# 32u4_Xbee_Shield.net
KiCad netlist of a schematic drawn in EAGLE
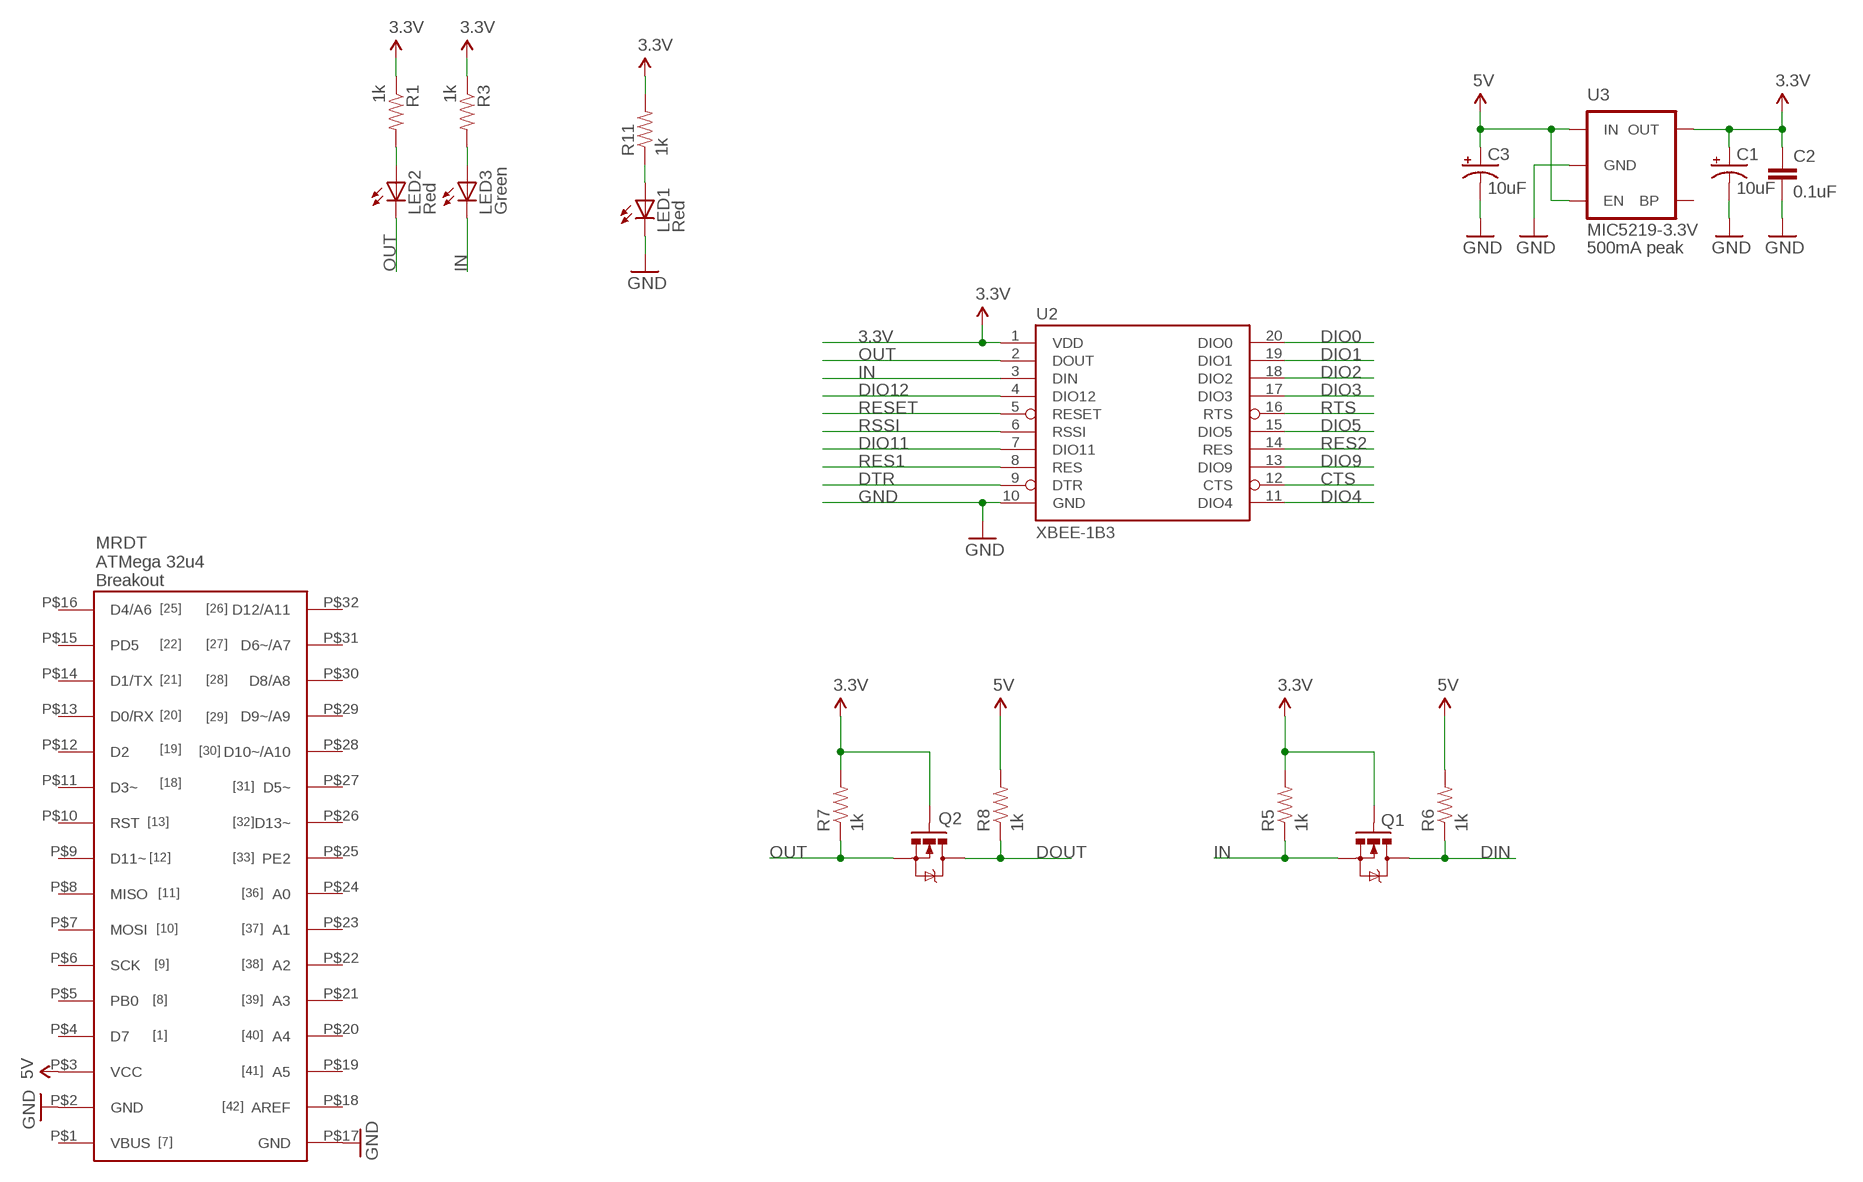
[diagram p0: schematic, sheet 1]

(export (version "E")
  (design (tool "Eeschema 10.0.6"))
  (components
    (comp (ref "C1")
      (value "10uF")
      (footprint "eagle-import:EIA3216")
      (libsource (lib "eagle-import") (part "CAP_POL1206"))
    )
    (comp (ref "C2")
      (value "0.1uF")
      (footprint "eagle-import:1206")
      (libsource (lib "eagle-import") (part "CAP1206"))
    )
    (comp (ref "C3")
      (value "10uF")
      (footprint "eagle-import:EIA3216")
      (libsource (lib "eagle-import") (part "CAP_POL1206"))
    )
    (comp (ref "LED1")
      (value "Red")
      (footprint "eagle-import:LED-0603")
      (libsource (lib "eagle-import") (part "LED0603"))
    )
    (comp (ref "LED2")
      (value "Red")
      (footprint "eagle-import:LED-0603")
      (libsource (lib "eagle-import") (part "LED0603"))
    )
    (comp (ref "LED3")
      (value "Green")
      (footprint "eagle-import:LED-0603")
      (libsource (lib "eagle-import") (part "LED0603"))
    )
    (comp (ref "Q1")
      (value "MOSFET-NCHANNELSMD")
      (footprint "eagle-import:SOT23-3")
      (libsource (lib "eagle-import") (part "MOSFET-NCHANNELSMD"))
    )
    (comp (ref "Q2")
      (value "MOSFET-NCHANNELSMD")
      (footprint "eagle-import:SOT23-3")
      (libsource (lib "eagle-import") (part "MOSFET-NCHANNELSMD"))
    )
    (comp (ref "R1")
      (value "1k")
      (footprint "eagle-import:1206")
      (libsource (lib "eagle-import") (part "RESISTOR1206"))
    )
    (comp (ref "R3")
      (value "1k")
      (footprint "eagle-import:1206")
      (libsource (lib "eagle-import") (part "RESISTOR1206"))
    )
    (comp (ref "R5")
      (value "1k")
      (footprint "eagle-import:1206")
      (libsource (lib "eagle-import") (part "RESISTOR1206"))
    )
    (comp (ref "R6")
      (value "1k")
      (footprint "eagle-import:1206")
      (libsource (lib "eagle-import") (part "RESISTOR1206"))
    )
    (comp (ref "R7")
      (value "1k")
      (footprint "eagle-import:1206")
      (libsource (lib "eagle-import") (part "RESISTOR1206"))
    )
    (comp (ref "R8")
      (value "1k")
      (footprint "eagle-import:1206")
      (libsource (lib "eagle-import") (part "RESISTOR1206"))
    )
    (comp (ref "R11")
      (value "1k")
      (footprint "eagle-import:1206")
      (libsource (lib "eagle-import") (part "RESISTOR1206"))
    )
    (comp (ref "U$1")
      (value "32U4_BREAKOU_SMD")
      (footprint "eagle-import:32U3_MCU_DIP_SMD")
      (libsource (lib "eagle-import") (part "32U4_BREAKOU_SMD"))
    )
    (comp (ref "U2")
      (value "XBEE-1B3")
      (footprint "eagle-import:XBEE-SMD")
      (libsource (lib "eagle-import") (part "XBEE-1B3"))
    )
    (comp (ref "U3")
      (value "V_REG_LDOSMD")
      (footprint "eagle-import:SOT23-5")
      (libsource (lib "eagle-import") (part "V_REG_LDOSMD"))
    )
  )
  (nets
    (net (code "1") (name "/CTS") (class "Default")
      (node (ref "U2") (pin "12") (pinfunction "CTS_12") (pintype "output"))
    )
    (net (code "2") (name "/DIN") (class "Default")
      (node (ref "Q1") (pin "3") (pinfunction "D_3") (pintype "passive"))
      (node (ref "R6") (pin "1") (pinfunction "1_1") (pintype "passive"))
    )
    (net (code "3") (name "/DIO0") (class "Default")
      (node (ref "U2") (pin "20") (pinfunction "DIO0_20") (pintype "bidirectional"))
    )
    (net (code "4") (name "/DIO1") (class "Default")
      (node (ref "U2") (pin "19") (pinfunction "DIO1_19") (pintype "bidirectional"))
    )
    (net (code "5") (name "/DIO2") (class "Default")
      (node (ref "U2") (pin "18") (pinfunction "DIO2_18") (pintype "bidirectional"))
    )
    (net (code "6") (name "/DIO3") (class "Default")
      (node (ref "U2") (pin "17") (pinfunction "DIO3_17") (pintype "bidirectional"))
    )
    (net (code "7") (name "/DIO4") (class "Default")
      (node (ref "U2") (pin "11") (pinfunction "DIO4_11") (pintype "bidirectional"))
    )
    (net (code "8") (name "/DIO5") (class "Default")
      (node (ref "U2") (pin "15") (pinfunction "DIO5_15") (pintype "bidirectional"))
    )
    (net (code "9") (name "/DIO9") (class "Default")
      (node (ref "U2") (pin "13") (pinfunction "DIO9_13") (pintype "bidirectional"))
    )
    (net (code "10") (name "/DIO11") (class "Default")
      (node (ref "U2") (pin "7") (pinfunction "DIO11_7") (pintype "bidirectional"))
    )
    (net (code "11") (name "/DIO12") (class "Default")
      (node (ref "U2") (pin "4") (pinfunction "DIO12_4") (pintype "bidirectional"))
    )
    (net (code "12") (name "/DOUT") (class "Default")
      (node (ref "Q2") (pin "3") (pinfunction "D_3") (pintype "passive"))
      (node (ref "R8") (pin "1") (pinfunction "1_1") (pintype "passive"))
    )
    (net (code "13") (name "/DTR") (class "Default")
      (node (ref "U2") (pin "9") (pinfunction "DTR_9") (pintype "bidirectional"))
    )
    (net (code "14") (name "/IN") (class "Default")
      (node (ref "LED3") (pin "C") (pinfunction "C_C") (pintype "passive"))
      (node (ref "Q1") (pin "2") (pinfunction "S_2") (pintype "passive"))
      (node (ref "R5") (pin "1") (pinfunction "1_1") (pintype "passive"))
      (node (ref "U2") (pin "3") (pinfunction "DIN_3") (pintype "input"))
    )
    (net (code "15") (name "/OUT") (class "Default")
      (node (ref "LED2") (pin "C") (pinfunction "C_C") (pintype "passive"))
      (node (ref "Q2") (pin "2") (pinfunction "S_2") (pintype "passive"))
      (node (ref "R7") (pin "1") (pinfunction "1_1") (pintype "passive"))
      (node (ref "U2") (pin "2") (pinfunction "DOUT_2") (pintype "output"))
    )
    (net (code "16") (name "/RES1") (class "Default")
      (node (ref "U2") (pin "8") (pinfunction "RES_8") (pintype "bidirectional"))
    )
    (net (code "17") (name "/RES2") (class "Default")
      (node (ref "U2") (pin "14") (pinfunction "RES_14") (pintype "bidirectional"))
    )
    (net (code "18") (name "/RESET") (class "Default")
      (node (ref "U2") (pin "5") (pinfunction "RESET_5") (pintype "input"))
    )
    (net (code "19") (name "/RSSI") (class "Default")
      (node (ref "U2") (pin "6") (pinfunction "RSSI_6") (pintype "bidirectional"))
    )
    (net (code "20") (name "/RTS") (class "Default")
      (node (ref "U2") (pin "16") (pinfunction "RTS_16") (pintype "input"))
    )
    (net (code "21") (name "3.3V") (class "Default")
      (node (ref "C1") (pin "A") (pinfunction "+_A") (pintype "passive"))
      (node (ref "C2") (pin "1") (pinfunction "1_1") (pintype "passive"))
      (node (ref "Q1") (pin "1") (pinfunction "G_1") (pintype "passive"))
      (node (ref "Q2") (pin "1") (pinfunction "G_1") (pintype "passive"))
      (node (ref "R1") (pin "1") (pinfunction "1_1") (pintype "passive"))
      (node (ref "R11") (pin "2") (pinfunction "2_2") (pintype "passive"))
      (node (ref "R3") (pin "1") (pinfunction "1_1") (pintype "passive"))
      (node (ref "R5") (pin "2") (pinfunction "2_2") (pintype "passive"))
      (node (ref "R7") (pin "2") (pinfunction "2_2") (pintype "passive"))
      (node (ref "U2") (pin "1") (pinfunction "VDD_1") (pintype "power_in"))
      (node (ref "U3") (pin "5") (pinfunction "OUT_5") (pintype "passive"))
    )
    (net (code "22") (name "5V") (class "Default")
      (node (ref "C3") (pin "A") (pinfunction "+_A") (pintype "passive"))
      (node (ref "R6") (pin "2") (pinfunction "2_2") (pintype "passive"))
      (node (ref "R8") (pin "2") (pinfunction "2_2") (pintype "passive"))
      (node (ref "U$1") (pin "P$3") (pinfunction "VCC_P$3") (pintype "bidirectional"))
      (node (ref "U3") (pin "1") (pinfunction "IN_1") (pintype "input"))
      (node (ref "U3") (pin "3") (pinfunction "EN_3") (pintype "input"))
    )
    (net (code "23") (name "GND") (class "Default")
      (node (ref "C1") (pin "C") (pinfunction "-_C") (pintype "passive"))
      (node (ref "C2") (pin "2") (pinfunction "2_2") (pintype "passive"))
      (node (ref "C3") (pin "C") (pinfunction "-_C") (pintype "passive"))
      (node (ref "LED1") (pin "C") (pinfunction "C_C") (pintype "passive"))
      (node (ref "U$1") (pin "P$17") (pinfunction "GND_P$17") (pintype "bidirectional"))
      (node (ref "U$1") (pin "P$2") (pinfunction "GND_P$2") (pintype "bidirectional"))
      (node (ref "U2") (pin "10") (pinfunction "GND_10") (pintype "power_in"))
      (node (ref "U3") (pin "2") (pinfunction "GND_2") (pintype "input"))
    )
    (net (code "24") (name "Net-(LED1-PadA)") (class "Default")
      (node (ref "LED1") (pin "A") (pinfunction "A_A") (pintype "passive"))
      (node (ref "R11") (pin "1") (pinfunction "1_1") (pintype "passive"))
    )
    (net (code "25") (name "Net-(LED2-PadA)") (class "Default")
      (node (ref "LED2") (pin "A") (pinfunction "A_A") (pintype "passive"))
      (node (ref "R1") (pin "2") (pinfunction "2_2") (pintype "passive"))
    )
    (net (code "26") (name "Net-(LED3-PadA)") (class "Default")
      (node (ref "LED3") (pin "A") (pinfunction "A_A") (pintype "passive"))
      (node (ref "R3") (pin "2") (pinfunction "2_2") (pintype "passive"))
    )
    (net (code "27") (name "unconnected-(U$1-A0-PadP$24)") (class "Default")
      (node (ref "U$1") (pin "P$24") (pinfunction "A0_P$24") (pintype "bidirectional"))
    )
    (net (code "28") (name "unconnected-(U$1-A1-PadP$23)") (class "Default")
      (node (ref "U$1") (pin "P$23") (pinfunction "A1_P$23") (pintype "bidirectional"))
    )
    (net (code "29") (name "unconnected-(U$1-A2-PadP$22)") (class "Default")
      (node (ref "U$1") (pin "P$22") (pinfunction "A2_P$22") (pintype "bidirectional"))
    )
    (net (code "30") (name "unconnected-(U$1-A3-PadP$21)") (class "Default")
      (node (ref "U$1") (pin "P$21") (pinfunction "A3_P$21") (pintype "bidirectional"))
    )
    (net (code "31") (name "unconnected-(U$1-A4-PadP$20)") (class "Default")
      (node (ref "U$1") (pin "P$20") (pinfunction "A4_P$20") (pintype "bidirectional"))
    )
    (net (code "32") (name "unconnected-(U$1-A5-PadP$19)") (class "Default")
      (node (ref "U$1") (pin "P$19") (pinfunction "A5_P$19") (pintype "bidirectional"))
    )
    (net (code "33") (name "unconnected-(U$1-AREF-PadP$18)") (class "Default")
      (node (ref "U$1") (pin "P$18") (pinfunction "AREF_P$18") (pintype "bidirectional"))
    )
    (net (code "34") (name "unconnected-(U$1-D0{slash}RX-PadP$13)") (class "Default")
      (node (ref "U$1") (pin "P$13") (pinfunction "D0/RX_P$13") (pintype "bidirectional"))
    )
    (net (code "35") (name "unconnected-(U$1-D1{slash}TX-PadP$14)") (class "Default")
      (node (ref "U$1") (pin "P$14") (pinfunction "D1/TX_P$14") (pintype "bidirectional"))
    )
    (net (code "36") (name "unconnected-(U$1-D2-PadP$12)") (class "Default")
      (node (ref "U$1") (pin "P$12") (pinfunction "D2_P$12") (pintype "bidirectional"))
    )
    (net (code "37") (name "unconnected-(U$1-D3~{}-PadP$11)") (class "Default")
      (node (ref "U$1") (pin "P$11") (pinfunction "D3~{}_P$11") (pintype "bidirectional"))
    )
    (net (code "38") (name "unconnected-(U$1-D4{slash}A6-PadP$16)") (class "Default")
      (node (ref "U$1") (pin "P$16") (pinfunction "D4/A6_P$16") (pintype "bidirectional"))
    )
    (net (code "39") (name "unconnected-(U$1-D5~{}-PadP$27)") (class "Default")
      (node (ref "U$1") (pin "P$27") (pinfunction "D5~{}_P$27") (pintype "bidirectional"))
    )
    (net (code "40") (name "unconnected-(U$1-D6~{{slash}A7}-PadP$31)") (class "Default")
      (node (ref "U$1") (pin "P$31") (pinfunction "D6~{/A7}_P$31") (pintype "bidirectional"))
    )
    (net (code "41") (name "unconnected-(U$1-D7-PadP$4)") (class "Default")
      (node (ref "U$1") (pin "P$4") (pinfunction "D7_P$4") (pintype "bidirectional"))
    )
    (net (code "42") (name "unconnected-(U$1-D8{slash}A8-PadP$30)") (class "Default")
      (node (ref "U$1") (pin "P$30") (pinfunction "D8/A8_P$30") (pintype "bidirectional"))
    )
    (net (code "43") (name "unconnected-(U$1-D9~{{slash}A9}-PadP$29)") (class "Default")
      (node (ref "U$1") (pin "P$29") (pinfunction "D9~{/A9}_P$29") (pintype "bidirectional"))
    )
    (net (code "44") (name "unconnected-(U$1-D10~{{slash}A10}-PadP$28)") (class "Default")
      (node (ref "U$1") (pin "P$28") (pinfunction "D10~{/A10}_P$28") (pintype "bidirectional"))
    )
    (net (code "45") (name "unconnected-(U$1-D11~{}-PadP$9)") (class "Default")
      (node (ref "U$1") (pin "P$9") (pinfunction "D11~{}_P$9") (pintype "bidirectional"))
    )
    (net (code "46") (name "unconnected-(U$1-D12{slash}A11-PadP$32)") (class "Default")
      (node (ref "U$1") (pin "P$32") (pinfunction "D12/A11_P$32") (pintype "bidirectional"))
    )
    (net (code "47") (name "unconnected-(U$1-D13~{}-PadP$26)") (class "Default")
      (node (ref "U$1") (pin "P$26") (pinfunction "D13~{}_P$26") (pintype "bidirectional"))
    )
    (net (code "48") (name "unconnected-(U$1-MISO-PadP$8)") (class "Default")
      (node (ref "U$1") (pin "P$8") (pinfunction "MISO_P$8") (pintype "bidirectional"))
    )
    (net (code "49") (name "unconnected-(U$1-MOSI-PadP$7)") (class "Default")
      (node (ref "U$1") (pin "P$7") (pinfunction "MOSI_P$7") (pintype "bidirectional"))
    )
    (net (code "50") (name "unconnected-(U$1-PB0-PadP$5)") (class "Default")
      (node (ref "U$1") (pin "P$5") (pinfunction "PB0_P$5") (pintype "bidirectional"))
    )
    (net (code "51") (name "unconnected-(U$1-PD5-PadP$15)") (class "Default")
      (node (ref "U$1") (pin "P$15") (pinfunction "PD5_P$15") (pintype "bidirectional"))
    )
    (net (code "52") (name "unconnected-(U$1-PE2-PadP$25)") (class "Default")
      (node (ref "U$1") (pin "P$25") (pinfunction "PE2_P$25") (pintype "bidirectional"))
    )
    (net (code "53") (name "unconnected-(U$1-RST-PadP$10)") (class "Default")
      (node (ref "U$1") (pin "P$10") (pinfunction "RST_P$10") (pintype "bidirectional"))
    )
    (net (code "54") (name "unconnected-(U$1-SCK-PadP$6)") (class "Default")
      (node (ref "U$1") (pin "P$6") (pinfunction "SCK_P$6") (pintype "bidirectional"))
    )
    (net (code "55") (name "unconnected-(U$1-VBUS-PadP$1)") (class "Default")
      (node (ref "U$1") (pin "P$1") (pinfunction "VBUS_P$1") (pintype "bidirectional"))
    )
    (net (code "56") (name "unconnected-(U3-BP-Pad4)") (class "Default")
      (node (ref "U3") (pin "4") (pinfunction "BP_4") (pintype "input"))
    )
  )
)
